# 1uO_c_v_1_3.net
KiCad netlist of a schematic drawn in EAGLE
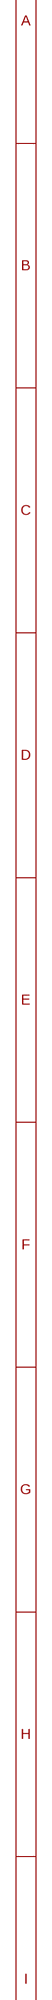
[diagram p0: schematic, sheet 1, part 1 of 2]
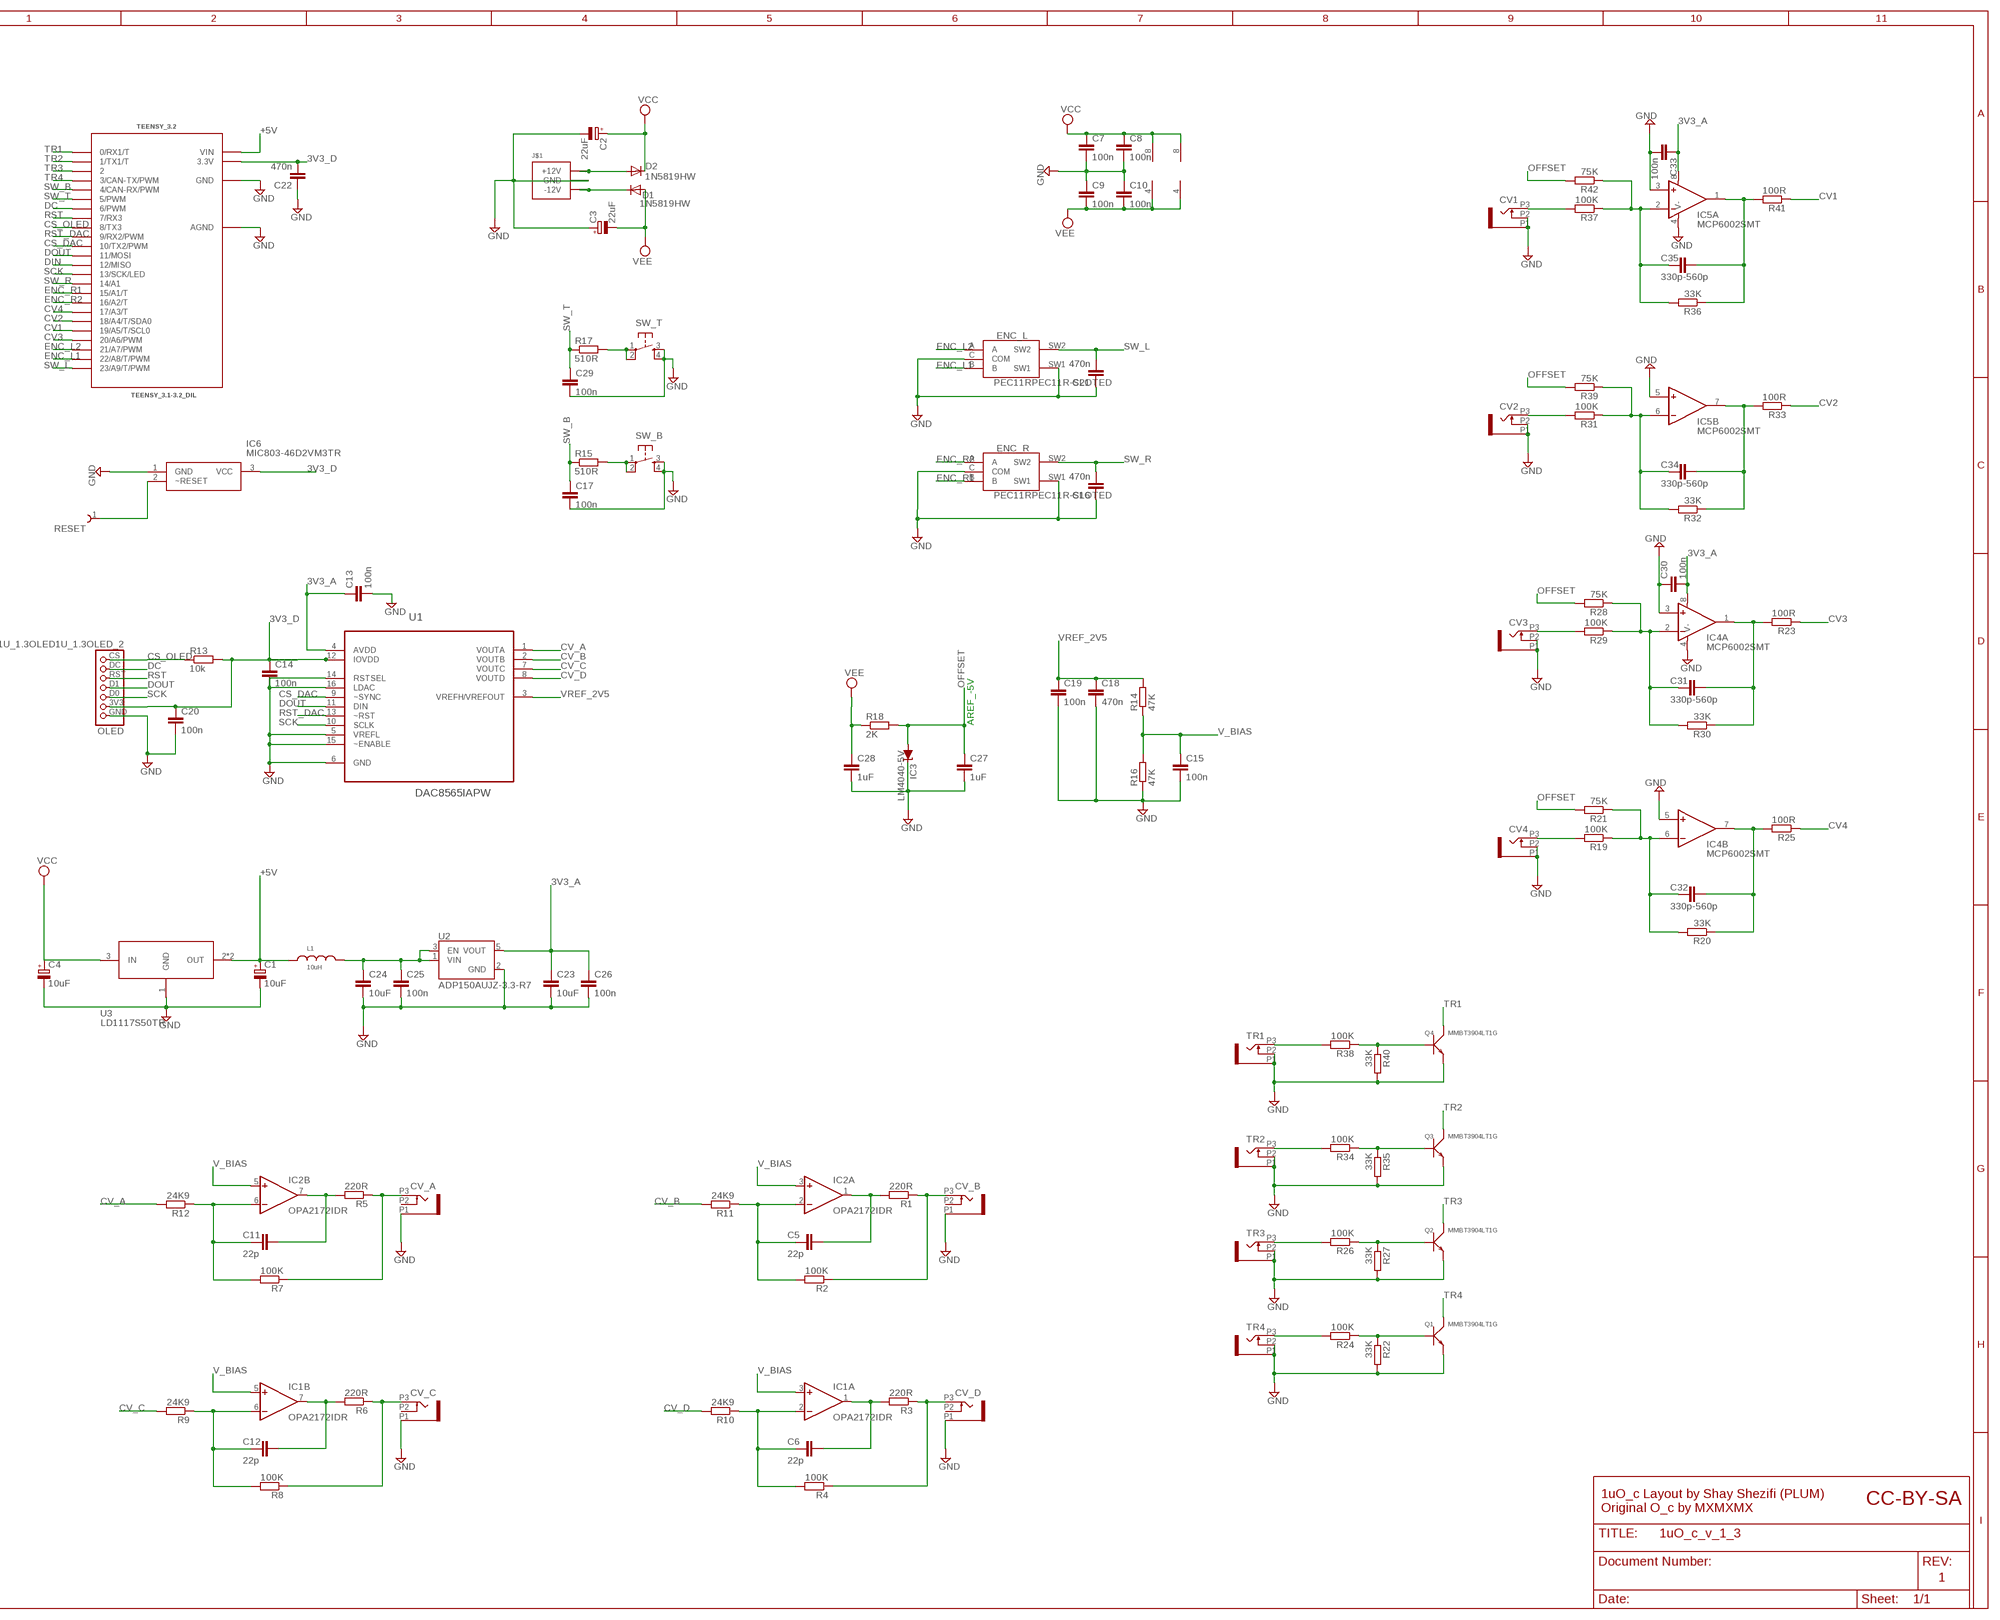
[diagram p1: schematic, sheet 1, part 2 of 2]

(export (version "E")
  (design (tool "Eeschema 10.0.6"))
  (components
    (comp (ref "C1")
      (value "10uF")
      (footprint "eagle-import:PANASONIC_B")
      (libsource (lib "eagle-import") (part "CPOL-EUB"))
    )
    (comp (ref "C2")
      (value "22uF")
      (footprint "eagle-import:PANASONIC_C")
      (libsource (lib "eagle-import") (part "CPOL-EUC"))
    )
    (comp (ref "C3")
      (value "22uF")
      (footprint "eagle-import:PANASONIC_C")
      (libsource (lib "eagle-import") (part "CPOL-EUC"))
    )
    (comp (ref "C4")
      (value "10uF")
      (footprint "eagle-import:PANASONIC_B")
      (libsource (lib "eagle-import") (part "CPOL-EUB"))
    )
    (comp (ref "C5")
      (value "22p")
      (footprint "eagle-import:C0603")
      (libsource (lib "eagle-import") (part "C-EUC0603"))
    )
    (comp (ref "C6")
      (value "22p")
      (footprint "eagle-import:C0603")
      (libsource (lib "eagle-import") (part "C-EUC0603"))
    )
    (comp (ref "C7")
      (value "100n")
      (footprint "eagle-import:C0603")
      (libsource (lib "eagle-import") (part "C-EUC0603"))
    )
    (comp (ref "C8")
      (value "100n")
      (footprint "eagle-import:C0603")
      (libsource (lib "eagle-import") (part "C-EUC0603"))
    )
    (comp (ref "C9")
      (value "100n")
      (footprint "eagle-import:C0603")
      (libsource (lib "eagle-import") (part "C-EUC0603"))
    )
    (comp (ref "C10")
      (value "100n")
      (footprint "eagle-import:C0603")
      (libsource (lib "eagle-import") (part "C-EUC0603"))
    )
    (comp (ref "C11")
      (value "22p")
      (footprint "eagle-import:C0603")
      (libsource (lib "eagle-import") (part "C-EUC0603"))
    )
    (comp (ref "C12")
      (value "22p")
      (footprint "eagle-import:C0603")
      (libsource (lib "eagle-import") (part "C-EUC0603"))
    )
    (comp (ref "C13")
      (value "100n")
      (footprint "eagle-import:C0603")
      (libsource (lib "eagle-import") (part "C-EUC0603"))
    )
    (comp (ref "C14")
      (value "100n")
      (footprint "eagle-import:C0603")
      (libsource (lib "eagle-import") (part "C-EUC0603"))
    )
    (comp (ref "C15")
      (value "100n")
      (footprint "eagle-import:C0603")
      (libsource (lib "eagle-import") (part "C-EUC0603"))
    )
    (comp (ref "C16")
      (value "470n")
      (footprint "eagle-import:C0603")
      (libsource (lib "eagle-import") (part "C-EUC0603"))
    )
    (comp (ref "C17")
      (value "100n")
      (footprint "eagle-import:C0603")
      (libsource (lib "eagle-import") (part "C-EUC0603"))
    )
    (comp (ref "C18")
      (value "470n")
      (footprint "eagle-import:C0603")
      (libsource (lib "eagle-import") (part "C-EUC0603"))
    )
    (comp (ref "C19")
      (value "100n")
      (footprint "eagle-import:C0603")
      (libsource (lib "eagle-import") (part "C-EUC0603"))
    )
    (comp (ref "C20")
      (value "100n")
      (footprint "eagle-import:C0603")
      (libsource (lib "eagle-import") (part "C-EUC0603"))
    )
    (comp (ref "C21")
      (value "470n")
      (footprint "eagle-import:C0603")
      (libsource (lib "eagle-import") (part "C-EUC0603"))
    )
    (comp (ref "C22")
      (value "470n")
      (footprint "eagle-import:C0603")
      (libsource (lib "eagle-import") (part "C-EUC0603"))
    )
    (comp (ref "C23")
      (value "10uF")
      (footprint "eagle-import:C1206K")
      (libsource (lib "eagle-import") (part "C-EUC1206K"))
    )
    (comp (ref "C24")
      (value "10uF")
      (footprint "eagle-import:C1206K")
      (libsource (lib "eagle-import") (part "C-EUC1206K"))
    )
    (comp (ref "C25")
      (value "100n")
      (footprint "eagle-import:C0603")
      (libsource (lib "eagle-import") (part "C-EUC0603"))
    )
    (comp (ref "C26")
      (value "100n")
      (footprint "eagle-import:C0603")
      (libsource (lib "eagle-import") (part "C-EUC0603"))
    )
    (comp (ref "C27")
      (value "1uF")
      (footprint "eagle-import:C0603")
      (libsource (lib "eagle-import") (part "C-EUC0603"))
    )
    (comp (ref "C28")
      (value "1uF")
      (footprint "eagle-import:C0603")
      (libsource (lib "eagle-import") (part "C-EUC0603"))
    )
    (comp (ref "C29")
      (value "100n")
      (footprint "eagle-import:C0603")
      (libsource (lib "eagle-import") (part "C-EUC0603"))
    )
    (comp (ref "C30")
      (value "100n")
      (footprint "eagle-import:C0603")
      (libsource (lib "eagle-import") (part "C-EUC0603"))
    )
    (comp (ref "C31")
      (value "330p-560p")
      (footprint "eagle-import:C0603")
      (libsource (lib "eagle-import") (part "C-EUC0603"))
    )
    (comp (ref "C32")
      (value "330p-560p")
      (footprint "eagle-import:C0603")
      (libsource (lib "eagle-import") (part "C-EUC0603"))
    )
    (comp (ref "C33")
      (value "100n")
      (footprint "eagle-import:C0603")
      (libsource (lib "eagle-import") (part "C-EUC0603"))
    )
    (comp (ref "C34")
      (value "330p-560p")
      (footprint "eagle-import:C0603")
      (libsource (lib "eagle-import") (part "C-EUC0603"))
    )
    (comp (ref "C35")
      (value "330p-560p")
      (footprint "eagle-import:C0603")
      (libsource (lib "eagle-import") (part "C-EUC0603"))
    )
    (comp (ref "CV1")
      (value "OG-PJ301_PJ301_THONKICONN")
      (footprint "eagle-import:OG-PJ301_WQP_PJ_301M6_NO_HOLE")
      (libsource (lib "eagle-import") (part "OG-PJ301_PJ301_THONKICONN"))
    )
    (comp (ref "CV2")
      (value "OG-PJ301_PJ301_THONKICONN")
      (footprint "eagle-import:OG-PJ301_WQP_PJ_301M6_NO_HOLE")
      (libsource (lib "eagle-import") (part "OG-PJ301_PJ301_THONKICONN"))
    )
    (comp (ref "CV3")
      (value "OG-PJ301_PJ301_THONKICONN")
      (footprint "eagle-import:OG-PJ301_WQP_PJ_301M6_NO_HOLE")
      (libsource (lib "eagle-import") (part "OG-PJ301_PJ301_THONKICONN"))
    )
    (comp (ref "CV4")
      (value "OG-PJ301_PJ301_THONKICONN")
      (footprint "eagle-import:OG-PJ301_WQP_PJ_301M6_NO_HOLE")
      (libsource (lib "eagle-import") (part "OG-PJ301_PJ301_THONKICONN"))
    )
    (comp (ref "CV_A")
      (value "OG-PJ301_PJ301_THONKICONN")
      (footprint "eagle-import:OG-PJ301_WQP_PJ_301M6_NO_HOLE")
      (libsource (lib "eagle-import") (part "OG-PJ301_PJ301_THONKICONN"))
    )
    (comp (ref "CV_B")
      (value "OG-PJ301_PJ301_THONKICONN")
      (footprint "eagle-import:OG-PJ301_WQP_PJ_301M6_NO_HOLE")
      (libsource (lib "eagle-import") (part "OG-PJ301_PJ301_THONKICONN"))
    )
    (comp (ref "CV_C")
      (value "OG-PJ301_PJ301_THONKICONN")
      (footprint "eagle-import:OG-PJ301_WQP_PJ_301M6_NO_HOLE")
      (libsource (lib "eagle-import") (part "OG-PJ301_PJ301_THONKICONN"))
    )
    (comp (ref "CV_D")
      (value "OG-PJ301_PJ301_THONKICONN")
      (footprint "eagle-import:OG-PJ301_WQP_PJ_301M6_NO_HOLE")
      (libsource (lib "eagle-import") (part "OG-PJ301_PJ301_THONKICONN"))
    )
    (comp (ref "D1")
      (value "1N5819HW")
      (footprint "eagle-import:DIODE_SOD123")
      (libsource (lib "eagle-import") (part "DIODE_DIODE-SOD123"))
    )
    (comp (ref "D2")
      (value "1N5819HW")
      (footprint "eagle-import:DIODE_SOD123")
      (libsource (lib "eagle-import") (part "DIODE_DIODE-SOD123"))
    )
    (comp (ref "ENC_L")
      (value "PEC11RPEC11R-SLOTED")
      (footprint "eagle-import:PEC11R-SLOTED")
      (libsource (lib "eagle-import") (part "PEC11RPEC11R-SLOTED"))
    )
    (comp (ref "ENC_R")
      (value "PEC11RPEC11R-SLOTED")
      (footprint "eagle-import:PEC11R-SLOTED")
      (libsource (lib "eagle-import") (part "PEC11RPEC11R-SLOTED"))
    )
    (comp (ref "IC1")
      (value "OPA2172IDR")
      (footprint "eagle-import:SO08")
      (libsource (lib "eagle-import") (part "TL072D"))
    )
    (comp (ref "IC2")
      (value "OPA2172IDR")
      (footprint "eagle-import:SO08")
      (libsource (lib "eagle-import") (part "TL072D"))
    )
    (comp (ref "IC3")
      (value "LM4040-5V")
      (footprint "eagle-import:DBZ_R-PDSO-G3")
      (libsource (lib "eagle-import") (part "LM4041DBZB12"))
    )
    (comp (ref "IC4")
      (value "MCP6002SMT")
      (footprint "eagle-import:SOIC8")
      (libsource (lib "eagle-import") (part "MCP6002SMT"))
    )
    (comp (ref "IC5")
      (value "MCP6002SMT")
      (footprint "eagle-import:SOIC8")
      (libsource (lib "eagle-import") (part "MCP6002SMT"))
    )
    (comp (ref "IC6")
      (value "MIC803-46D2VM3TR")
      (footprint "eagle-import:SOT95P230X110-3N")
      (libsource (lib "eagle-import") (part "MIC803-46D2VM3TR"))
    )
    (comp (ref "J$1")
      (value "POWER_SIMPLE10")
      (footprint "eagle-import:POWER_10")
      (libsource (lib "eagle-import") (part "POWER_SIMPLE10"))
    )
    (comp (ref "L1")
      (value "10uH")
      (footprint "eagle-import:WE-LQ_M")
      (libsource (lib "eagle-import") (part "WE-LQ_1210_744032001"))
    )
    (comp (ref "OLED")
      (value "1U_1.3OLED1U_1.3OLED_2")
      (footprint "eagle-import:1U_1.3OLED_2")
      (libsource (lib "eagle-import") (part "1U_1.3OLED1U_1.3OLED_2"))
    )
    (comp (ref "Q1")
      (value "MMBT3904LT1G")
      (footprint "eagle-import:SOT-23")
      (libsource (lib "eagle-import") (part "SMD-TRANSISTORS-NPN-40V-200MA-MMBT3904LT1G(SOT-23)"))
    )
    (comp (ref "Q2")
      (value "MMBT3904LT1G")
      (footprint "eagle-import:SOT-23")
      (libsource (lib "eagle-import") (part "SMD-TRANSISTORS-NPN-40V-200MA-MMBT3904LT1G(SOT-23)"))
    )
    (comp (ref "Q3")
      (value "MMBT3904LT1G")
      (footprint "eagle-import:SOT-23")
      (libsource (lib "eagle-import") (part "SMD-TRANSISTORS-NPN-40V-200MA-MMBT3904LT1G(SOT-23)"))
    )
    (comp (ref "Q4")
      (value "MMBT3904LT1G")
      (footprint "eagle-import:SOT-23")
      (libsource (lib "eagle-import") (part "SMD-TRANSISTORS-NPN-40V-200MA-MMBT3904LT1G(SOT-23)"))
    )
    (comp (ref "R1")
      (value "220R")
      (footprint "eagle-import:R0603")
      (libsource (lib "eagle-import") (part "R-EU_R0603"))
    )
    (comp (ref "R2")
      (value "100K")
      (footprint "eagle-import:R0603")
      (libsource (lib "eagle-import") (part "R-EU_R0603"))
    )
    (comp (ref "R3")
      (value "220R")
      (footprint "eagle-import:R0603")
      (libsource (lib "eagle-import") (part "R-EU_R0603"))
    )
    (comp (ref "R4")
      (value "100K")
      (footprint "eagle-import:R0603")
      (libsource (lib "eagle-import") (part "R-EU_R0603"))
    )
    (comp (ref "R5")
      (value "220R")
      (footprint "eagle-import:R0603")
      (libsource (lib "eagle-import") (part "R-EU_R0603"))
    )
    (comp (ref "R6")
      (value "220R")
      (footprint "eagle-import:R0603")
      (libsource (lib "eagle-import") (part "R-EU_R0603"))
    )
    (comp (ref "R7")
      (value "100K")
      (footprint "eagle-import:R0603")
      (libsource (lib "eagle-import") (part "R-EU_R0603"))
    )
    (comp (ref "R8")
      (value "100K")
      (footprint "eagle-import:R0603")
      (libsource (lib "eagle-import") (part "R-EU_R0603"))
    )
    (comp (ref "R9")
      (value "24K9")
      (footprint "eagle-import:R0603")
      (libsource (lib "eagle-import") (part "R-EU_R0603"))
    )
    (comp (ref "R10")
      (value "24K9")
      (footprint "eagle-import:R0603")
      (libsource (lib "eagle-import") (part "R-EU_R0603"))
    )
    (comp (ref "R11")
      (value "24K9")
      (footprint "eagle-import:R0603")
      (libsource (lib "eagle-import") (part "R-EU_R0603"))
    )
    (comp (ref "R12")
      (value "24K9")
      (footprint "eagle-import:R0603")
      (libsource (lib "eagle-import") (part "R-EU_R0603"))
    )
    (comp (ref "R13")
      (value "10k")
      (footprint "eagle-import:R0603")
      (libsource (lib "eagle-import") (part "R-EU_R0603"))
    )
    (comp (ref "R14")
      (value "47K")
      (footprint "eagle-import:R0603")
      (libsource (lib "eagle-import") (part "R-EU_R0603"))
    )
    (comp (ref "R15")
      (value "510R")
      (footprint "eagle-import:R0603")
      (libsource (lib "eagle-import") (part "R-EU_R0603"))
    )
    (comp (ref "R16")
      (value "47K")
      (footprint "eagle-import:R0603")
      (libsource (lib "eagle-import") (part "R-EU_R0603"))
    )
    (comp (ref "R17")
      (value "510R")
      (footprint "eagle-import:R0603")
      (libsource (lib "eagle-import") (part "R-EU_R0603"))
    )
    (comp (ref "R18")
      (value "2K")
      (footprint "eagle-import:R0603")
      (libsource (lib "eagle-import") (part "R-EU_R0603"))
    )
    (comp (ref "R19")
      (value "100K")
      (footprint "eagle-import:R0603")
      (libsource (lib "eagle-import") (part "R-EU_R0603"))
    )
    (comp (ref "R20")
      (value "33K")
      (footprint "eagle-import:R0603")
      (libsource (lib "eagle-import") (part "R-EU_R0603"))
    )
    (comp (ref "R21")
      (value "75K")
      (footprint "eagle-import:R0603")
      (libsource (lib "eagle-import") (part "R-EU_R0603"))
    )
    (comp (ref "R22")
      (value "33K")
      (footprint "eagle-import:R0603")
      (libsource (lib "eagle-import") (part "R-EU_R0603"))
    )
    (comp (ref "R23")
      (value "100R")
      (footprint "eagle-import:R0603")
      (libsource (lib "eagle-import") (part "R-EU_R0603"))
    )
    (comp (ref "R24")
      (value "100K")
      (footprint "eagle-import:R0603")
      (libsource (lib "eagle-import") (part "R-EU_R0603"))
    )
    (comp (ref "R25")
      (value "100R")
      (footprint "eagle-import:R0603")
      (libsource (lib "eagle-import") (part "R-EU_R0603"))
    )
    (comp (ref "R26")
      (value "100K")
      (footprint "eagle-import:R0603")
      (libsource (lib "eagle-import") (part "R-EU_R0603"))
    )
    (comp (ref "R27")
      (value "33K")
      (footprint "eagle-import:R0603")
      (libsource (lib "eagle-import") (part "R-EU_R0603"))
    )
    (comp (ref "R28")
      (value "75K")
      (footprint "eagle-import:R0603")
      (libsource (lib "eagle-import") (part "R-EU_R0603"))
    )
    (comp (ref "R29")
      (value "100K")
      (footprint "eagle-import:R0603")
      (libsource (lib "eagle-import") (part "R-EU_R0603"))
    )
    (comp (ref "R30")
      (value "33K")
      (footprint "eagle-import:R0603")
      (libsource (lib "eagle-import") (part "R-EU_R0603"))
    )
    (comp (ref "R31")
      (value "100K")
      (footprint "eagle-import:R0603")
      (libsource (lib "eagle-import") (part "R-EU_R0603"))
    )
    (comp (ref "R32")
      (value "33K")
      (footprint "eagle-import:R0603")
      (libsource (lib "eagle-import") (part "R-EU_R0603"))
    )
    (comp (ref "R33")
      (value "100R")
      (footprint "eagle-import:R0603")
      (libsource (lib "eagle-import") (part "R-EU_R0603"))
    )
    (comp (ref "R34")
      (value "100K")
      (footprint "eagle-import:R0603")
      (libsource (lib "eagle-import") (part "R-EU_R0603"))
    )
    (comp (ref "R35")
      (value "33K")
      (footprint "eagle-import:R0603")
      (libsource (lib "eagle-import") (part "R-EU_R0603"))
    )
    (comp (ref "R36")
      (value "33K")
      (footprint "eagle-import:R0603")
      (libsource (lib "eagle-import") (part "R-EU_R0603"))
    )
    (comp (ref "R37")
      (value "100K")
      (footprint "eagle-import:R0603")
      (libsource (lib "eagle-import") (part "R-EU_R0603"))
    )
    (comp (ref "R38")
      (value "100K")
      (footprint "eagle-import:R0603")
      (libsource (lib "eagle-import") (part "R-EU_R0603"))
    )
    (comp (ref "R39")
      (value "75K")
      (footprint "eagle-import:R0603")
      (libsource (lib "eagle-import") (part "R-EU_R0603"))
    )
    (comp (ref "R40")
      (value "33K")
      (footprint "eagle-import:R0603")
      (libsource (lib "eagle-import") (part "R-EU_R0603"))
    )
    (comp (ref "R41")
      (value "100R")
      (footprint "eagle-import:R0603")
      (libsource (lib "eagle-import") (part "R-EU_R0603"))
    )
    (comp (ref "R42")
      (value "75K")
      (footprint "eagle-import:R0603")
      (libsource (lib "eagle-import") (part "R-EU_R0603"))
    )
    (comp (ref "RESET")
      (value "61300111121")
      (footprint "eagle-import:61300111121")
      (libsource (lib "eagle-import") (part "61300111121"))
    )
    (comp (ref "SW_B")
      (value "TAC_SWITCHPTH")
      (footprint "eagle-import:TACTILE-PTH")
      (libsource (lib "eagle-import") (part "TAC_SWITCHPTH"))
    )
    (comp (ref "SW_T")
      (value "TAC_SWITCHPTH")
      (footprint "eagle-import:TACTILE-PTH")
      (libsource (lib "eagle-import") (part "TAC_SWITCHPTH"))
    )
    (comp (ref "TEENSY_3.2")
      (value "TEENSY_3.1-3.2_DIL")
      (footprint "eagle-import:TEENSY_3.0-3.2&LC_DIL")
      (libsource (lib "eagle-import") (part "TEENSY_3.1-3.2_DIL"))
    )
    (comp (ref "TR1")
      (value "OG-PJ301_PJ301_THONKICONN")
      (footprint "eagle-import:OG-PJ301_WQP_PJ_301M6_NO_HOLE")
      (libsource (lib "eagle-import") (part "OG-PJ301_PJ301_THONKICONN"))
    )
    (comp (ref "TR2")
      (value "OG-PJ301_PJ301_THONKICONN")
      (footprint "eagle-import:OG-PJ301_WQP_PJ_301M6_NO_HOLE")
      (libsource (lib "eagle-import") (part "OG-PJ301_PJ301_THONKICONN"))
    )
    (comp (ref "TR3")
      (value "OG-PJ301_PJ301_THONKICONN")
      (footprint "eagle-import:OG-PJ301_WQP_PJ_301M6_NO_HOLE")
      (libsource (lib "eagle-import") (part "OG-PJ301_PJ301_THONKICONN"))
    )
    (comp (ref "TR4")
      (value "OG-PJ301_PJ301_THONKICONN")
      (footprint "eagle-import:OG-PJ301_WQP_PJ_301M6_NO_HOLE")
      (libsource (lib "eagle-import") (part "OG-PJ301_PJ301_THONKICONN"))
    )
    (comp (ref "U1")
      (value "DAC8565IAPW")
      (footprint "eagle-import:SOP65P640X120-16N")
      (fields (field (name "MF") "Texas Instruments"))
      (libsource (lib "eagle-import") (part "DAC8565IAPW"))
    )
    (comp (ref "U2")
      (value "ADP150AUJZ-3.3-R7")
      (footprint "eagle-import:SOT95P280X100-5N")
      (fields (field (name "MF") "Analog Devices") (field (name "MP") "ADP150AUJZ-2.0-R7"))
      (libsource (lib "eagle-import") (part "ADP150AUJZ-3.3-R7"))
    )
    (comp (ref "U3")
      (value "LD1117S50TR")
      (footprint "eagle-import:SOT223")
      (fields (field (name "MF") "STMicroelectronics"))
      (libsource (lib "eagle-import") (part "LD1117S50TR"))
    )
  )
  (nets
    (net (code "1") (name "/+5V") (class "Default")
      (node (ref "C1") (pin "+") (pinfunction "+_+") (pintype "passive"))
      (node (ref "L1") (pin "1") (pinfunction "1_1") (pintype "passive"))
      (node (ref "TEENSY_3.2") (pin "VIN") (pinfunction "VIN_VIN") (pintype "power_in"))
      (node (ref "U3") (pin "2") (pinfunction "OUT_2") (pintype "output"))
      (node (ref "U3") (pin "4") (pinfunction "OUT_4") (pintype "output"))
    )
    (net (code "2") (name "/3V3_A") (class "Default")
      (node (ref "C13") (pin "1") (pinfunction "1_1") (pintype "passive"))
      (node (ref "C23") (pin "1") (pinfunction "1_1") (pintype "passive"))
      (node (ref "C26") (pin "1") (pinfunction "1_1") (pintype "passive"))
      (node (ref "C30") (pin "2") (pinfunction "2_2") (pintype "passive"))
      (node (ref "C33") (pin "1") (pinfunction "1_1") (pintype "passive"))
      (node (ref "IC4") (pin "8") (pinfunction "V+_8") (pintype "power_in"))
      (node (ref "IC5") (pin "8") (pinfunction "V+_8") (pintype "power_in"))
      (node (ref "U1") (pin "4") (pinfunction "AVDD_4") (pintype "power_in"))
      (node (ref "U2") (pin "5") (pinfunction "VOUT_5") (pintype "output"))
    )
    (net (code "3") (name "/3V3_D") (class "Default")
      (node (ref "C14") (pin "1") (pinfunction "1_1") (pintype "passive"))
      (node (ref "C20") (pin "1") (pinfunction "1_1") (pintype "passive"))
      (node (ref "C22") (pin "2") (pinfunction "2_2") (pintype "passive"))
      (node (ref "IC6") (pin "3") (pinfunction "VCC_3") (pintype "bidirectional"))
      (node (ref "OLED") (pin "3V3") (pinfunction "3V3_3V3") (pintype "passive"))
      (node (ref "R13") (pin "2") (pinfunction "2_2") (pintype "passive"))
      (node (ref "TEENSY_3.2") (pin "3.3V") (pinfunction "3.3V_3.3V") (pintype "power_in"))
      (node (ref "U1") (pin "12") (pinfunction "IOVDD_12") (pintype "power_in"))
    )
    (net (code "4") (name "/CS_DAC") (class "Default")
      (node (ref "TEENSY_3.2") (pin "10") (pinfunction "10/TX2/PWM_10") (pintype "bidirectional"))
      (node (ref "U1") (pin "9") (pinfunction "~{SYNC}_9") (pintype "input"))
    )
    (net (code "5") (name "/CS_OLED") (class "Default")
      (node (ref "OLED") (pin "CS") (pinfunction "CS_CS") (pintype "passive"))
      (node (ref "R13") (pin "1") (pinfunction "1_1") (pintype "passive"))
      (node (ref "TEENSY_3.2") (pin "8") (pinfunction "8/TX3_8") (pintype "bidirectional"))
    )
    (net (code "6") (name "/CV1") (class "Default")
      (node (ref "R41") (pin "1") (pinfunction "1_1") (pintype "passive"))
      (node (ref "TEENSY_3.2") (pin "19/A5") (pinfunction "19/A5/T/SCL0_19/A5") (pintype "bidirectional"))
    )
    (net (code "7") (name "/CV2") (class "Default")
      (node (ref "R33") (pin "1") (pinfunction "1_1") (pintype "passive"))
      (node (ref "TEENSY_3.2") (pin "18/A4") (pinfunction "18/A4/T/SDA0_18/A4") (pintype "bidirectional"))
    )
    (net (code "8") (name "/CV3") (class "Default")
      (node (ref "R23") (pin "1") (pinfunction "1_1") (pintype "passive"))
      (node (ref "TEENSY_3.2") (pin "20/A6") (pinfunction "20/A6/PWM_20/A6") (pintype "bidirectional"))
    )
    (net (code "9") (name "/CV4") (class "Default")
      (node (ref "R25") (pin "1") (pinfunction "1_1") (pintype "passive"))
      (node (ref "TEENSY_3.2") (pin "17/A3") (pinfunction "17/A3/T_17/A3") (pintype "bidirectional"))
    )
    (net (code "10") (name "/CV_A") (class "Default")
      (node (ref "R12") (pin "2") (pinfunction "2_2") (pintype "passive"))
      (node (ref "U1") (pin "1") (pinfunction "VOUTA_1") (pintype "output"))
    )
    (net (code "11") (name "/CV_B") (class "Default")
      (node (ref "R11") (pin "2") (pinfunction "2_2") (pintype "passive"))
      (node (ref "U1") (pin "2") (pinfunction "VOUTB_2") (pintype "output"))
    )
    (net (code "12") (name "/CV_C") (class "Default")
      (node (ref "R9") (pin "2") (pinfunction "2_2") (pintype "passive"))
      (node (ref "U1") (pin "7") (pinfunction "VOUTC_7") (pintype "output"))
    )
    (net (code "13") (name "/CV_D") (class "Default")
      (node (ref "R10") (pin "2") (pinfunction "2_2") (pintype "passive"))
      (node (ref "U1") (pin "8") (pinfunction "VOUTD_8") (pintype "output"))
    )
    (net (code "14") (name "/DC") (class "Default")
      (node (ref "OLED") (pin "DC") (pinfunction "DC_DC") (pintype "passive"))
      (node (ref "TEENSY_3.2") (pin "6") (pinfunction "6/PWM_6") (pintype "bidirectional"))
    )
    (net (code "15") (name "/DIN") (class "Default")
      (node (ref "TEENSY_3.2") (pin "12") (pinfunction "12/MISO_12") (pintype "bidirectional"))
    )
    (net (code "16") (name "/DOUT") (class "Default")
      (node (ref "OLED") (pin "D1") (pinfunction "D1_D1") (pintype "passive"))
      (node (ref "TEENSY_3.2") (pin "11") (pinfunction "11/MOSI_11") (pintype "bidirectional"))
      (node (ref "U1") (pin "11") (pinfunction "DIN_11") (pintype "input"))
    )
    (net (code "17") (name "/ENC_L1") (class "Default")
      (node (ref "ENC_L") (pin "B") (pinfunction "B_B") (pintype "bidirectional"))
      (node (ref "TEENSY_3.2") (pin "22/A8") (pinfunction "22/A8/T/PWM_22/A8") (pintype "bidirectional"))
    )
    (net (code "18") (name "/ENC_L2") (class "Default")
      (node (ref "ENC_L") (pin "A") (pinfunction "A_A") (pintype "bidirectional"))
      (node (ref "TEENSY_3.2") (pin "21/A7") (pinfunction "21/A7/PWM_21/A7") (pintype "bidirectional"))
    )
    (net (code "19") (name "/ENC_R1") (class "Default")
      (node (ref "ENC_R") (pin "B") (pinfunction "B_B") (pintype "bidirectional"))
      (node (ref "TEENSY_3.2") (pin "15/A1") (pinfunction "15/A1/T_15/A1") (pintype "bidirectional"))
    )
    (net (code "20") (name "/ENC_R2") (class "Default")
      (node (ref "ENC_R") (pin "A") (pinfunction "A_A") (pintype "bidirectional"))
      (node (ref "TEENSY_3.2") (pin "16/A2") (pinfunction "16/A2/T_16/A2") (pintype "bidirectional"))
    )
    (net (code "21") (name "/OFFSET") (class "Default")
      (node (ref "C27") (pin "1") (pinfunction "1_1") (pintype "passive"))
      (node (ref "IC3") (pin "2") (pinfunction "A_2") (pintype "passive"))
      (node (ref "R18") (pin "2") (pinfunction "2_2") (pintype "passive"))
      (node (ref "R21") (pin "2") (pinfunction "2_2") (pintype "passive"))
      (node (ref "R28") (pin "2") (pinfunction "2_2") (pintype "passive"))
      (node (ref "R39") (pin "2") (pinfunction "2_2") (pintype "passive"))
      (node (ref "R42") (pin "2") (pinfunction "2_2") (pintype "passive"))
    )
    (net (code "22") (name "/RST") (class "Default")
      (node (ref "OLED") (pin "RST") (pinfunction "RST_RST") (pintype "passive"))
      (node (ref "TEENSY_3.2") (pin "7") (pinfunction "7/RX3_7") (pintype "bidirectional"))
    )
    (net (code "23") (name "/RST_DAC") (class "Default")
      (node (ref "TEENSY_3.2") (pin "9") (pinfunction "9/RX2/PWM_9") (pintype "bidirectional"))
      (node (ref "U1") (pin "13") (pinfunction "~{RST}_13") (pintype "input"))
    )
    (net (code "24") (name "/SCK") (class "Default")
      (node (ref "OLED") (pin "D0") (pinfunction "D0_D0") (pintype "passive"))
      (node (ref "TEENSY_3.2") (pin "13") (pinfunction "13/SCK/LED_13") (pintype "bidirectional"))
      (node (ref "U1") (pin "10") (pinfunction "SCLK_10") (pintype "input"))
    )
    (net (code "25") (name "/SW_B") (class "Default")
      (node (ref "C17") (pin "1") (pinfunction "1_1") (pintype "passive"))
      (node (ref "R15") (pin "1") (pinfunction "1_1") (pintype "passive"))
      (node (ref "TEENSY_3.2") (pin "4") (pinfunction "4/CAN-RX/PWM_4") (pintype "bidirectional"))
    )
    (net (code "26") (name "/SW_L") (class "Default")
      (node (ref "C21") (pin "2") (pinfunction "2_2") (pintype "passive"))
      (node (ref "ENC_L") (pin "SW2") (pinfunction "SW2_SW2") (pintype "bidirectional"))
      (node (ref "TEENSY_3.2") (pin "23/A9") (pinfunction "23/A9/T/PWM_23/A9") (pintype "bidirectional"))
    )
    (net (code "27") (name "/SW_R") (class "Default")
      (node (ref "C16") (pin "2") (pinfunction "2_2") (pintype "passive"))
      (node (ref "ENC_R") (pin "SW2") (pinfunction "SW2_SW2") (pintype "bidirectional"))
      (node (ref "TEENSY_3.2") (pin "14/A0") (pinfunction "14/A1_14/A0") (pintype "bidirectional"))
    )
    (net (code "28") (name "/SW_T") (class "Default")
      (node (ref "C29") (pin "1") (pinfunction "1_1") (pintype "passive"))
      (node (ref "R17") (pin "1") (pinfunction "1_1") (pintype "passive"))
      (node (ref "TEENSY_3.2") (pin "5") (pinfunction "5/PWM_5") (pintype "bidirectional"))
    )
    (net (code "29") (name "/TR1") (class "Default")
      (node (ref "Q4") (pin "3") (pinfunction "C_3") (pintype "passive"))
      (node (ref "TEENSY_3.2") (pin "0") (pinfunction "0/RX1/T_0") (pintype "bidirectional"))
    )
    (net (code "30") (name "/TR2") (class "Default")
      (node (ref "Q3") (pin "3") (pinfunction "C_3") (pintype "passive"))
      (node (ref "TEENSY_3.2") (pin "1") (pinfunction "1/TX1/T_1") (pintype "bidirectional"))
    )
    (net (code "31") (name "/TR3") (class "Default")
      (node (ref "Q2") (pin "3") (pinfunction "C_3") (pintype "passive"))
      (node (ref "TEENSY_3.2") (pin "2") (pinfunction "2_2") (pintype "bidirectional"))
    )
    (net (code "32") (name "/TR4") (class "Default")
      (node (ref "Q1") (pin "3") (pinfunction "C_3") (pintype "passive"))
      (node (ref "TEENSY_3.2") (pin "3") (pinfunction "3/CAN-TX/PWM_3") (pintype "bidirectional"))
    )
    (net (code "33") (name "/VREF_2V5") (class "Default")
      (node (ref "C18") (pin "1") (pinfunction "1_1") (pintype "passive"))
      (node (ref "C19") (pin "1") (pinfunction "1_1") (pintype "passive"))
      (node (ref "R14") (pin "2") (pinfunction "2_2") (pintype "passive"))
      (node (ref "U1") (pin "3") (pinfunction "VREFH/VREFOUT_3") (pintype "bidirectional"))
    )
    (net (code "34") (name "/V_BIAS") (class "Default")
      (node (ref "C15") (pin "1") (pinfunction "1_1") (pintype "passive"))
      (node (ref "IC1") (pin "3") (pinfunction "+IN_3") (pintype "input"))
      (node (ref "IC1") (pin "5") (pinfunction "+IN_5") (pintype "input"))
      (node (ref "IC2") (pin "3") (pinfunction "+IN_3") (pintype "input"))
      (node (ref "IC2") (pin "5") (pinfunction "+IN_5") (pintype "input"))
      (node (ref "R14") (pin "1") (pinfunction "1_1") (pintype "passive"))
      (node (ref "R16") (pin "2") (pinfunction "2_2") (pintype "passive"))
    )
    (net (code "35") (name "GND") (class "Default")
      (node (ref "C1") (pin "-") (pinfunction "-_-") (pintype "passive"))
      (node (ref "C10") (pin "1") (pinfunction "1_1") (pintype "passive"))
      (node (ref "C13") (pin "2") (pinfunction "2_2") (pintype "passive"))
      (node (ref "C14") (pin "2") (pinfunction "2_2") (pintype "passive"))
      (node (ref "C15") (pin "2") (pinfunction "2_2") (pintype "passive"))
      (node (ref "C16") (pin "1") (pinfunction "1_1") (pintype "passive"))
      (node (ref "C17") (pin "2") (pinfunction "2_2") (pintype "passive"))
      (node (ref "C18") (pin "2") (pinfunction "2_2") (pintype "passive"))
      (node (ref "C19") (pin "2") (pinfunction "2_2") (pintype "passive"))
      (node (ref "C2") (pin "-") (pinfunction "-_-") (pintype "passive"))
      (node (ref "C20") (pin "2") (pinfunction "2_2") (pintype "passive"))
      (node (ref "C21") (pin "1") (pinfunction "1_1") (pintype "passive"))
      (node (ref "C22") (pin "1") (pinfunction "1_1") (pintype "passive"))
      (node (ref "C23") (pin "2") (pinfunction "2_2") (pintype "passive"))
      (node (ref "C24") (pin "2") (pinfunction "2_2") (pintype "passive"))
      (node (ref "C25") (pin "2") (pinfunction "2_2") (pintype "passive"))
      (node (ref "C26") (pin "2") (pinfunction "2_2") (pintype "passive"))
      (node (ref "C27") (pin "2") (pinfunction "2_2") (pintype "passive"))
      (node (ref "C28") (pin "2") (pinfunction "2_2") (pintype "passive"))
      (node (ref "C29") (pin "2") (pinfunction "2_2") (pintype "passive"))
      (node (ref "C3") (pin "+") (pinfunction "+_+") (pintype "passive"))
      (node (ref "C30") (pin "1") (pinfunction "1_1") (pintype "passive"))
      (node (ref "C33") (pin "2") (pinfunction "2_2") (pintype "passive"))
      (node (ref "C4") (pin "-") (pinfunction "-_-") (pintype "passive"))
      (node (ref "C7") (pin "2") (pinfunction "2_2") (pintype "passive"))
      (node (ref "C8") (pin "2") (pinfunction "2_2") (pintype "passive"))
      (node (ref "C9") (pin "1") (pinfunction "1_1") (pintype "passive"))
      (node (ref "CV1") (pin "P1") (pinfunction "1_P1") (pintype "passive"))
      (node (ref "CV1") (pin "P2") (pinfunction "2_P2") (pintype "passive"))
      (node (ref "CV2") (pin "P1") (pinfunction "1_P1") (pintype "passive"))
      (node (ref "CV2") (pin "P2") (pinfunction "2_P2") (pintype "passive"))
      (node (ref "CV3") (pin "P1") (pinfunction "1_P1") (pintype "passive"))
      (node (ref "CV3") (pin "P2") (pinfunction "2_P2") (pintype "passive"))
      (node (ref "CV4") (pin "P1") (pinfunction "1_P1") (pintype "passive"))
      (node (ref "CV4") (pin "P2") (pinfunction "2_P2") (pintype "passive"))
      (node (ref "CV_A") (pin "P1") (pinfunction "1_P1") (pintype "passive"))
      (node (ref "CV_B") (pin "P1") (pinfunction "1_P1") (pintype "passive"))
      (node (ref "CV_C") (pin "P1") (pinfunction "1_P1") (pintype "passive"))
      (node (ref "CV_D") (pin "P1") (pinfunction "1_P1") (pintype "passive"))
      (node (ref "ENC_L") (pin "C") (pinfunction "COM_C") (pintype "bidirectional"))
      (node (ref "ENC_L") (pin "SW1") (pinfunction "SW1_SW1") (pintype "bidirectional"))
      (node (ref "ENC_R") (pin "C") (pinfunction "COM_C") (pintype "bidirectional"))
      (node (ref "ENC_R") (pin "SW1") (pinfunction "SW1_SW1") (pintype "bidirectional"))
      (node (ref "IC3") (pin "1") (pinfunction "C_1") (pintype "passive"))
      (node (ref "IC4") (pin "3") (pinfunction "+IN_3") (pintype "input"))
      (node (ref "IC4") (pin "4") (pinfunction "V-_4") (pintype "power_in"))
      (node (ref "IC4") (pin "5") (pinfunction "+IN_5") (pintype "input"))
      (node (ref "IC5") (pin "3") (pinfunction "+IN_3") (pintype "input"))
      (node (ref "IC5") (pin "4") (pinfunction "V-_4") (pintype "power_in"))
      (node (ref "IC5") (pin "5") (pinfunction "+IN_5") (pintype "input"))
      (node (ref "IC6") (pin "1") (pinfunction "GND_1") (pintype "bidirectional"))
      (node (ref "J$1") (pin "3") (pinfunction "GND_3") (pintype "bidirectional"))
      (node (ref "J$1") (pin "4") (pinfunction "GND_4") (pintype "bidirectional"))
      (node (ref "J$1") (pin "5") (pinfunction "GND_5") (pintype "bidirectional"))
      (node (ref "J$1") (pin "6") (pinfunction "GND_6") (pintype "bidirectional"))
      (node (ref "J$1") (pin "7") (pinfunction "GND_7") (pintype "bidirectional"))
      (node (ref "J$1") (pin "8") (pinfunction "GND_8") (pintype "bidirectional"))
      (node (ref "OLED") (pin "GND") (pinfunction "GND_GND") (pintype "passive"))
      (node (ref "Q1") (pin "2") (pinfunction "E_2") (pintype "passive"))
      (node (ref "Q2") (pin "2") (pinfunction "E_2") (pintype "passive"))
      (node (ref "Q3") (pin "2") (pinfunction "E_2") (pintype "passive"))
      (node (ref "Q4") (pin "2") (pinfunction "E_2") (pintype "passive"))
      (node (ref "R16") (pin "1") (pinfunction "1_1") (pintype "passive"))
      (node (ref "R22") (pin "2") (pinfunction "2_2") (pintype "passive"))
      (node (ref "R27") (pin "2") (pinfunction "2_2") (pintype "passive"))
      (node (ref "R35") (pin "2") (pinfunction "2_2") (pintype "passive"))
      (node (ref "R40") (pin "2") (pinfunction "2_2") (pintype "passive"))
      (node (ref "SW_B") (pin "3") (pinfunction "3_3") (pintype "passive"))
      (node (ref "SW_B") (pin "4") (pinfunction "4_4") (pintype "passive"))
      (node (ref "SW_T") (pin "3") (pinfunction "3_3") (pintype "passive"))
      (node (ref "SW_T") (pin "4") (pinfunction "4_4") (pintype "passive"))
      (node (ref "TEENSY_3.2") (pin "AGND") (pinfunction "AGND_AGND") (pintype "power_in"))
      (node (ref "TEENSY_3.2") (pin "GND") (pinfunction "GND_GND") (pintype "power_in"))
      (node (ref "TR1") (pin "P1") (pinfunction "1_P1") (pintype "passive"))
      (node (ref "TR1") (pin "P2") (pinfunction "2_P2") (pintype "passive"))
      (node (ref "TR2") (pin "P1") (pinfunction "1_P1") (pintype "passive"))
      (node (ref "TR2") (pin "P2") (pinfunction "2_P2") (pintype "passive"))
      (node (ref "TR3") (pin "P1") (pinfunction "1_P1") (pintype "passive"))
      (node (ref "TR3") (pin "P2") (pinfunction "2_P2") (pintype "passive"))
      (node (ref "TR4") (pin "P1") (pinfunction "1_P1") (pintype "passive"))
      (node (ref "TR4") (pin "P2") (pinfunction "2_P2") (pintype "passive"))
      (node (ref "U1") (pin "14") (pinfunction "RSTSEL_14") (pintype "input"))
      (node (ref "U1") (pin "15") (pinfunction "~{ENABLE}_15") (pintype "input"))
      (node (ref "U1") (pin "16") (pinfunction "LDAC_16") (pintype "input"))
      (node (ref "U1") (pin "5") (pinfunction "VREFL_5") (pintype "input"))
      (node (ref "U1") (pin "6") (pinfunction "GND_6") (pintype "passive"))
      (node (ref "U2") (pin "2") (pinfunction "GND_2") (pintype "power_in"))
      (node (ref "U3") (pin "1") (pinfunction "GND_1") (pintype "passive"))
    )
    (net (code "36") (name "Net-(CV1-3)") (class "Default")
      (node (ref "CV1") (pin "P3") (pinfunction "3_P3") (pintype "passive"))
      (node (ref "R37") (pin "2") (pinfunction "2_2") (pintype "passive"))
    )
    (net (code "37") (name "Net-(CV2-3)") (class "Default")
      (node (ref "CV2") (pin "P3") (pinfunction "3_P3") (pintype "passive"))
      (node (ref "R31") (pin "2") (pinfunction "2_2") (pintype "passive"))
    )
    (net (code "38") (name "Net-(CV3-3)") (class "Default")
      (node (ref "CV3") (pin "P3") (pinfunction "3_P3") (pintype "passive"))
      (node (ref "R29") (pin "2") (pinfunction "2_2") (pintype "passive"))
    )
    (net (code "39") (name "Net-(CV4-3)") (class "Default")
      (node (ref "CV4") (pin "P3") (pinfunction "3_P3") (pintype "passive"))
      (node (ref "R19") (pin "2") (pinfunction "2_2") (pintype "passive"))
    )
    (net (code "40") (name "Net-(CV_A-3)") (class "Default")
      (node (ref "CV_A") (pin "P3") (pinfunction "3_P3") (pintype "passive"))
      (node (ref "R5") (pin "1") (pinfunction "1_1") (pintype "passive"))
      (node (ref "R7") (pin "1") (pinfunction "1_1") (pintype "passive"))
    )
    (net (code "41") (name "Net-(CV_B-3)") (class "Default")
      (node (ref "CV_B") (pin "P3") (pinfunction "3_P3") (pintype "passive"))
      (node (ref "R1") (pin "1") (pinfunction "1_1") (pintype "passive"))
      (node (ref "R2") (pin "1") (pinfunction "1_1") (pintype "passive"))
    )
    (net (code "42") (name "Net-(CV_C-3)") (class "Default")
      (node (ref "CV_C") (pin "P3") (pinfunction "3_P3") (pintype "passive"))
      (node (ref "R6") (pin "1") (pinfunction "1_1") (pintype "passive"))
      (node (ref "R8") (pin "1") (pinfunction "1_1") (pintype "passive"))
    )
    (net (code "43") (name "Net-(CV_D-3)") (class "Default")
      (node (ref "CV_D") (pin "P3") (pinfunction "3_P3") (pintype "passive"))
      (node (ref "R3") (pin "1") (pinfunction "1_1") (pintype "passive"))
      (node (ref "R4") (pin "1") (pinfunction "1_1") (pintype "passive"))
    )
    (net (code "44") (name "Net-(D1-PadC)") (class "Default")
      (node (ref "D1") (pin "C") (pinfunction "C_C") (pintype "passive"))
      (node (ref "J$1") (pin "1") (pinfunction "-12V_1") (pintype "bidirectional"))
      (node (ref "J$1") (pin "2") (pinfunction "-12V_2") (pintype "bidirectional"))
    )
    (net (code "45") (name "Net-(D2-PadA)") (class "Default")
      (node (ref "D2") (pin "A") (pinfunction "A_A") (pintype "passive"))
      (node (ref "J$1") (pin "10") (pinfunction "+12V_10") (pintype "bidirectional"))
      (node (ref "J$1") (pin "9") (pinfunction "+12V_9") (pintype "bidirectional"))
    )
    (net (code "46") (name "Net-(IC1A--IN)") (class "Default")
      (node (ref "C6") (pin "2") (pinfunction "2_2") (pintype "passive"))
      (node (ref "IC1") (pin "2") (pinfunction "-IN_2") (pintype "input"))
      (node (ref "R10") (pin "1") (pinfunction "1_1") (pintype "passive"))
      (node (ref "R4") (pin "2") (pinfunction "2_2") (pintype "passive"))
    )
    (net (code "47") (name "Net-(IC1A-OUT)") (class "Default")
      (node (ref "C6") (pin "1") (pinfunction "1_1") (pintype "passive"))
      (node (ref "IC1") (pin "1") (pinfunction "OUT_1") (pintype "output"))
      (node (ref "R3") (pin "2") (pinfunction "2_2") (pintype "passive"))
    )
    (net (code "48") (name "Net-(IC1B--IN)") (class "Default")
      (node (ref "C12") (pin "2") (pinfunction "2_2") (pintype "passive"))
      (node (ref "IC1") (pin "6") (pinfunction "-IN_6") (pintype "input"))
      (node (ref "R8") (pin "2") (pinfunction "2_2") (pintype "passive"))
      (node (ref "R9") (pin "1") (pinfunction "1_1") (pintype "passive"))
    )
    (net (code "49") (name "Net-(IC1B-OUT)") (class "Default")
      (node (ref "C12") (pin "1") (pinfunction "1_1") (pintype "passive"))
      (node (ref "IC1") (pin "7") (pinfunction "OUT_7") (pintype "output"))
      (node (ref "R6") (pin "2") (pinfunction "2_2") (pintype "passive"))
    )
    (net (code "50") (name "Net-(IC2A--IN)") (class "Default")
      (node (ref "C5") (pin "2") (pinfunction "2_2") (pintype "passive"))
      (node (ref "IC2") (pin "2") (pinfunction "-IN_2") (pintype "input"))
      (node (ref "R11") (pin "1") (pinfunction "1_1") (pintype "passive"))
      (node (ref "R2") (pin "2") (pinfunction "2_2") (pintype "passive"))
    )
    (net (code "51") (name "Net-(IC2A-OUT)") (class "Default")
      (node (ref "C5") (pin "1") (pinfunction "1_1") (pintype "passive"))
      (node (ref "IC2") (pin "1") (pinfunction "OUT_1") (pintype "output"))
      (node (ref "R1") (pin "2") (pinfunction "2_2") (pintype "passive"))
    )
    (net (code "52") (name "Net-(IC2B--IN)") (class "Default")
      (node (ref "C11") (pin "2") (pinfunction "2_2") (pintype "passive"))
      (node (ref "IC2") (pin "6") (pinfunction "-IN_6") (pintype "input"))
      (node (ref "R12") (pin "1") (pinfunction "1_1") (pintype "passive"))
      (node (ref "R7") (pin "2") (pinfunction "2_2") (pintype "passive"))
    )
    (net (code "53") (name "Net-(IC2B-OUT)") (class "Default")
      (node (ref "C11") (pin "1") (pinfunction "1_1") (pintype "passive"))
      (node (ref "IC2") (pin "7") (pinfunction "OUT_7") (pintype "output"))
      (node (ref "R5") (pin "2") (pinfunction "2_2") (pintype "passive"))
    )
    (net (code "54") (name "Net-(IC4A--IN)") (class "Default")
      (node (ref "C31") (pin "2") (pinfunction "2_2") (pintype "passive"))
      (node (ref "IC4") (pin "2") (pinfunction "-IN_2") (pintype "input"))
      (node (ref "R28") (pin "1") (pinfunction "1_1") (pintype "passive"))
      (node (ref "R29") (pin "1") (pinfunction "1_1") (pintype "passive"))
      (node (ref "R30") (pin "2") (pinfunction "2_2") (pintype "passive"))
    )
    (net (code "55") (name "Net-(IC4A-OUT)") (class "Default")
      (node (ref "C31") (pin "1") (pinfunction "1_1") (pintype "passive"))
      (node (ref "IC4") (pin "1") (pinfunction "OUT_1") (pintype "output"))
      (node (ref "R23") (pin "2") (pinfunction "2_2") (pintype "passive"))
      (node (ref "R30") (pin "1") (pinfunction "1_1") (pintype "passive"))
    )
    (net (code "56") (name "Net-(IC4B--IN)") (class "Default")
      (node (ref "C32") (pin "2") (pinfunction "2_2") (pintype "passive"))
      (node (ref "IC4") (pin "6") (pinfunction "-IN_6") (pintype "input"))
      (node (ref "R19") (pin "1") (pinfunction "1_1") (pintype "passive"))
      (node (ref "R20") (pin "2") (pinfunction "2_2") (pintype "passive"))
      (node (ref "R21") (pin "1") (pinfunction "1_1") (pintype "passive"))
    )
    (net (code "57") (name "Net-(IC4B-OUT)") (class "Default")
      (node (ref "C32") (pin "1") (pinfunction "1_1") (pintype "passive"))
      (node (ref "IC4") (pin "7") (pinfunction "OUT_7") (pintype "output"))
      (node (ref "R20") (pin "1") (pinfunction "1_1") (pintype "passive"))
      (node (ref "R25") (pin "2") (pinfunction "2_2") (pintype "passive"))
    )
    (net (code "58") (name "Net-(IC5A--IN)") (class "Default")
      (node (ref "C35") (pin "2") (pinfunction "2_2") (pintype "passive"))
      (node (ref "IC5") (pin "2") (pinfunction "-IN_2") (pintype "input"))
      (node (ref "R36") (pin "2") (pinfunction "2_2") (pintype "passive"))
      (node (ref "R37") (pin "1") (pinfunction "1_1") (pintype "passive"))
      (node (ref "R42") (pin "1") (pinfunction "1_1") (pintype "passive"))
    )
    (net (code "59") (name "Net-(IC5A-OUT)") (class "Default")
      (node (ref "C35") (pin "1") (pinfunction "1_1") (pintype "passive"))
      (node (ref "IC5") (pin "1") (pinfunction "OUT_1") (pintype "output"))
      (node (ref "R36") (pin "1") (pinfunction "1_1") (pintype "passive"))
      (node (ref "R41") (pin "2") (pinfunction "2_2") (pintype "passive"))
    )
    (net (code "60") (name "Net-(IC5B--IN)") (class "Default")
      (node (ref "C34") (pin "2") (pinfunction "2_2") (pintype "passive"))
      (node (ref "IC5") (pin "6") (pinfunction "-IN_6") (pintype "input"))
      (node (ref "R31") (pin "1") (pinfunction "1_1") (pintype "passive"))
      (node (ref "R32") (pin "2") (pinfunction "2_2") (pintype "passive"))
      (node (ref "R39") (pin "1") (pinfunction "1_1") (pintype "passive"))
    )
    (net (code "61") (name "Net-(IC5B-OUT)") (class "Default")
      (node (ref "C34") (pin "1") (pinfunction "1_1") (pintype "passive"))
      (node (ref "IC5") (pin "7") (pinfunction "OUT_7") (pintype "output"))
      (node (ref "R32") (pin "1") (pinfunction "1_1") (pintype "passive"))
      (node (ref "R33") (pin "2") (pinfunction "2_2") (pintype "passive"))
    )
    (net (code "62") (name "Net-(IC6-~{RESET})") (class "Default")
      (node (ref "IC6") (pin "2") (pinfunction "~{RESET}_2") (pintype "bidirectional"))
      (node (ref "RESET") (pin "1") (pinfunction "1_1") (pintype "passive"))
    )
    (net (code "63") (name "Net-(Q1-B)") (class "Default")
      (node (ref "Q1") (pin "1") (pinfunction "B_1") (pintype "passive"))
      (node (ref "R22") (pin "1") (pinfunction "1_1") (pintype "passive"))
      (node (ref "R24") (pin "1") (pinfunction "1_1") (pintype "passive"))
    )
    (net (code "64") (name "Net-(Q2-B)") (class "Default")
      (node (ref "Q2") (pin "1") (pinfunction "B_1") (pintype "passive"))
      (node (ref "R26") (pin "1") (pinfunction "1_1") (pintype "passive"))
      (node (ref "R27") (pin "1") (pinfunction "1_1") (pintype "passive"))
    )
    (net (code "65") (name "Net-(Q3-B)") (class "Default")
      (node (ref "Q3") (pin "1") (pinfunction "B_1") (pintype "passive"))
      (node (ref "R34") (pin "1") (pinfunction "1_1") (pintype "passive"))
      (node (ref "R35") (pin "1") (pinfunction "1_1") (pintype "passive"))
    )
    (net (code "66") (name "Net-(Q4-B)") (class "Default")
      (node (ref "Q4") (pin "1") (pinfunction "B_1") (pintype "passive"))
      (node (ref "R38") (pin "1") (pinfunction "1_1") (pintype "passive"))
      (node (ref "R40") (pin "1") (pinfunction "1_1") (pintype "passive"))
    )
    (net (code "67") (name "Net-(R15-Pad2)") (class "Default")
      (node (ref "R15") (pin "2") (pinfunction "2_2") (pintype "passive"))
      (node (ref "SW_B") (pin "1") (pinfunction "1_1") (pintype "passive"))
      (node (ref "SW_B") (pin "2") (pinfunction "2_2") (pintype "passive"))
    )
    (net (code "68") (name "Net-(R17-Pad2)") (class "Default")
      (node (ref "R17") (pin "2") (pinfunction "2_2") (pintype "passive"))
      (node (ref "SW_T") (pin "1") (pinfunction "1_1") (pintype "passive"))
      (node (ref "SW_T") (pin "2") (pinfunction "2_2") (pintype "passive"))
    )
    (net (code "69") (name "Net-(TR1-3)") (class "Default")
      (node (ref "R38") (pin "2") (pinfunction "2_2") (pintype "passive"))
      (node (ref "TR1") (pin "P3") (pinfunction "3_P3") (pintype "passive"))
    )
    (net (code "70") (name "Net-(TR2-3)") (class "Default")
      (node (ref "R34") (pin "2") (pinfunction "2_2") (pintype "passive"))
      (node (ref "TR2") (pin "P3") (pinfunction "3_P3") (pintype "passive"))
    )
    (net (code "71") (name "Net-(TR3-3)") (class "Default")
      (node (ref "R26") (pin "2") (pinfunction "2_2") (pintype "passive"))
      (node (ref "TR3") (pin "P3") (pinfunction "3_P3") (pintype "passive"))
    )
    (net (code "72") (name "Net-(TR4-3)") (class "Default")
      (node (ref "R24") (pin "2") (pinfunction "2_2") (pintype "passive"))
      (node (ref "TR4") (pin "P3") (pinfunction "3_P3") (pintype "passive"))
    )
    (net (code "73") (name "Net-(U2-EN)") (class "Default")
      (node (ref "C24") (pin "1") (pinfunction "1_1") (pintype "passive"))
      (node (ref "C25") (pin "1") (pinfunction "1_1") (pintype "passive"))
      (node (ref "L1") (pin "2") (pinfunction "2_2") (pintype "passive"))
      (node (ref "U2") (pin "1") (pinfunction "VIN_1") (pintype "input"))
      (node (ref "U2") (pin "3") (pinfunction "EN_3") (pintype "input"))
    )
    (net (code "74") (name "VCC") (class "Default")
      (node (ref "C2") (pin "+") (pinfunction "+_+") (pintype "passive"))
      (node (ref "C4") (pin "+") (pinfunction "+_+") (pintype "passive"))
      (node (ref "C7") (pin "1") (pinfunction "1_1") (pintype "passive"))
      (node (ref "C8") (pin "1") (pinfunction "1_1") (pintype "passive"))
      (node (ref "D2") (pin "C") (pinfunction "C_C") (pintype "passive"))
      (node (ref "IC1") (pin "8") (pinfunction "V+_8") (pintype "power_in"))
      (node (ref "IC2") (pin "8") (pinfunction "V+_8") (pintype "power_in"))
      (node (ref "U3") (pin "3") (pinfunction "IN_3") (pintype "input"))
    )
    (net (code "75") (name "VEE") (class "Default")
      (node (ref "C10") (pin "2") (pinfunction "2_2") (pintype "passive"))
      (node (ref "C28") (pin "1") (pinfunction "1_1") (pintype "passive"))
      (node (ref "C3") (pin "-") (pinfunction "-_-") (pintype "passive"))
      (node (ref "C9") (pin "2") (pinfunction "2_2") (pintype "passive"))
      (node (ref "D1") (pin "A") (pinfunction "A_A") (pintype "passive"))
      (node (ref "IC1") (pin "4") (pinfunction "V-_4") (pintype "power_in"))
      (node (ref "IC2") (pin "4") (pinfunction "V-_4") (pintype "power_in"))
      (node (ref "R18") (pin "1") (pinfunction "1_1") (pintype "passive"))
    )
    (net (code "76") (name "unconnected-(CV_A-2-PadP2)") (class "Default")
      (node (ref "CV_A") (pin "P2") (pinfunction "2_P2") (pintype "passive"))
    )
    (net (code "77") (name "unconnected-(CV_B-2-PadP2)") (class "Default")
      (node (ref "CV_B") (pin "P2") (pinfunction "2_P2") (pintype "passive"))
    )
    (net (code "78") (name "unconnected-(CV_C-2-PadP2)") (class "Default")
      (node (ref "CV_C") (pin "P2") (pinfunction "2_P2") (pintype "passive"))
    )
    (net (code "79") (name "unconnected-(CV_D-2-PadP2)") (class "Default")
      (node (ref "CV_D") (pin "P2") (pinfunction "2_P2") (pintype "passive"))
    )
  )
)
